# Adafruit_RA8875_TFT_Breakout.net
KiCad netlist of a schematic drawn in EAGLE
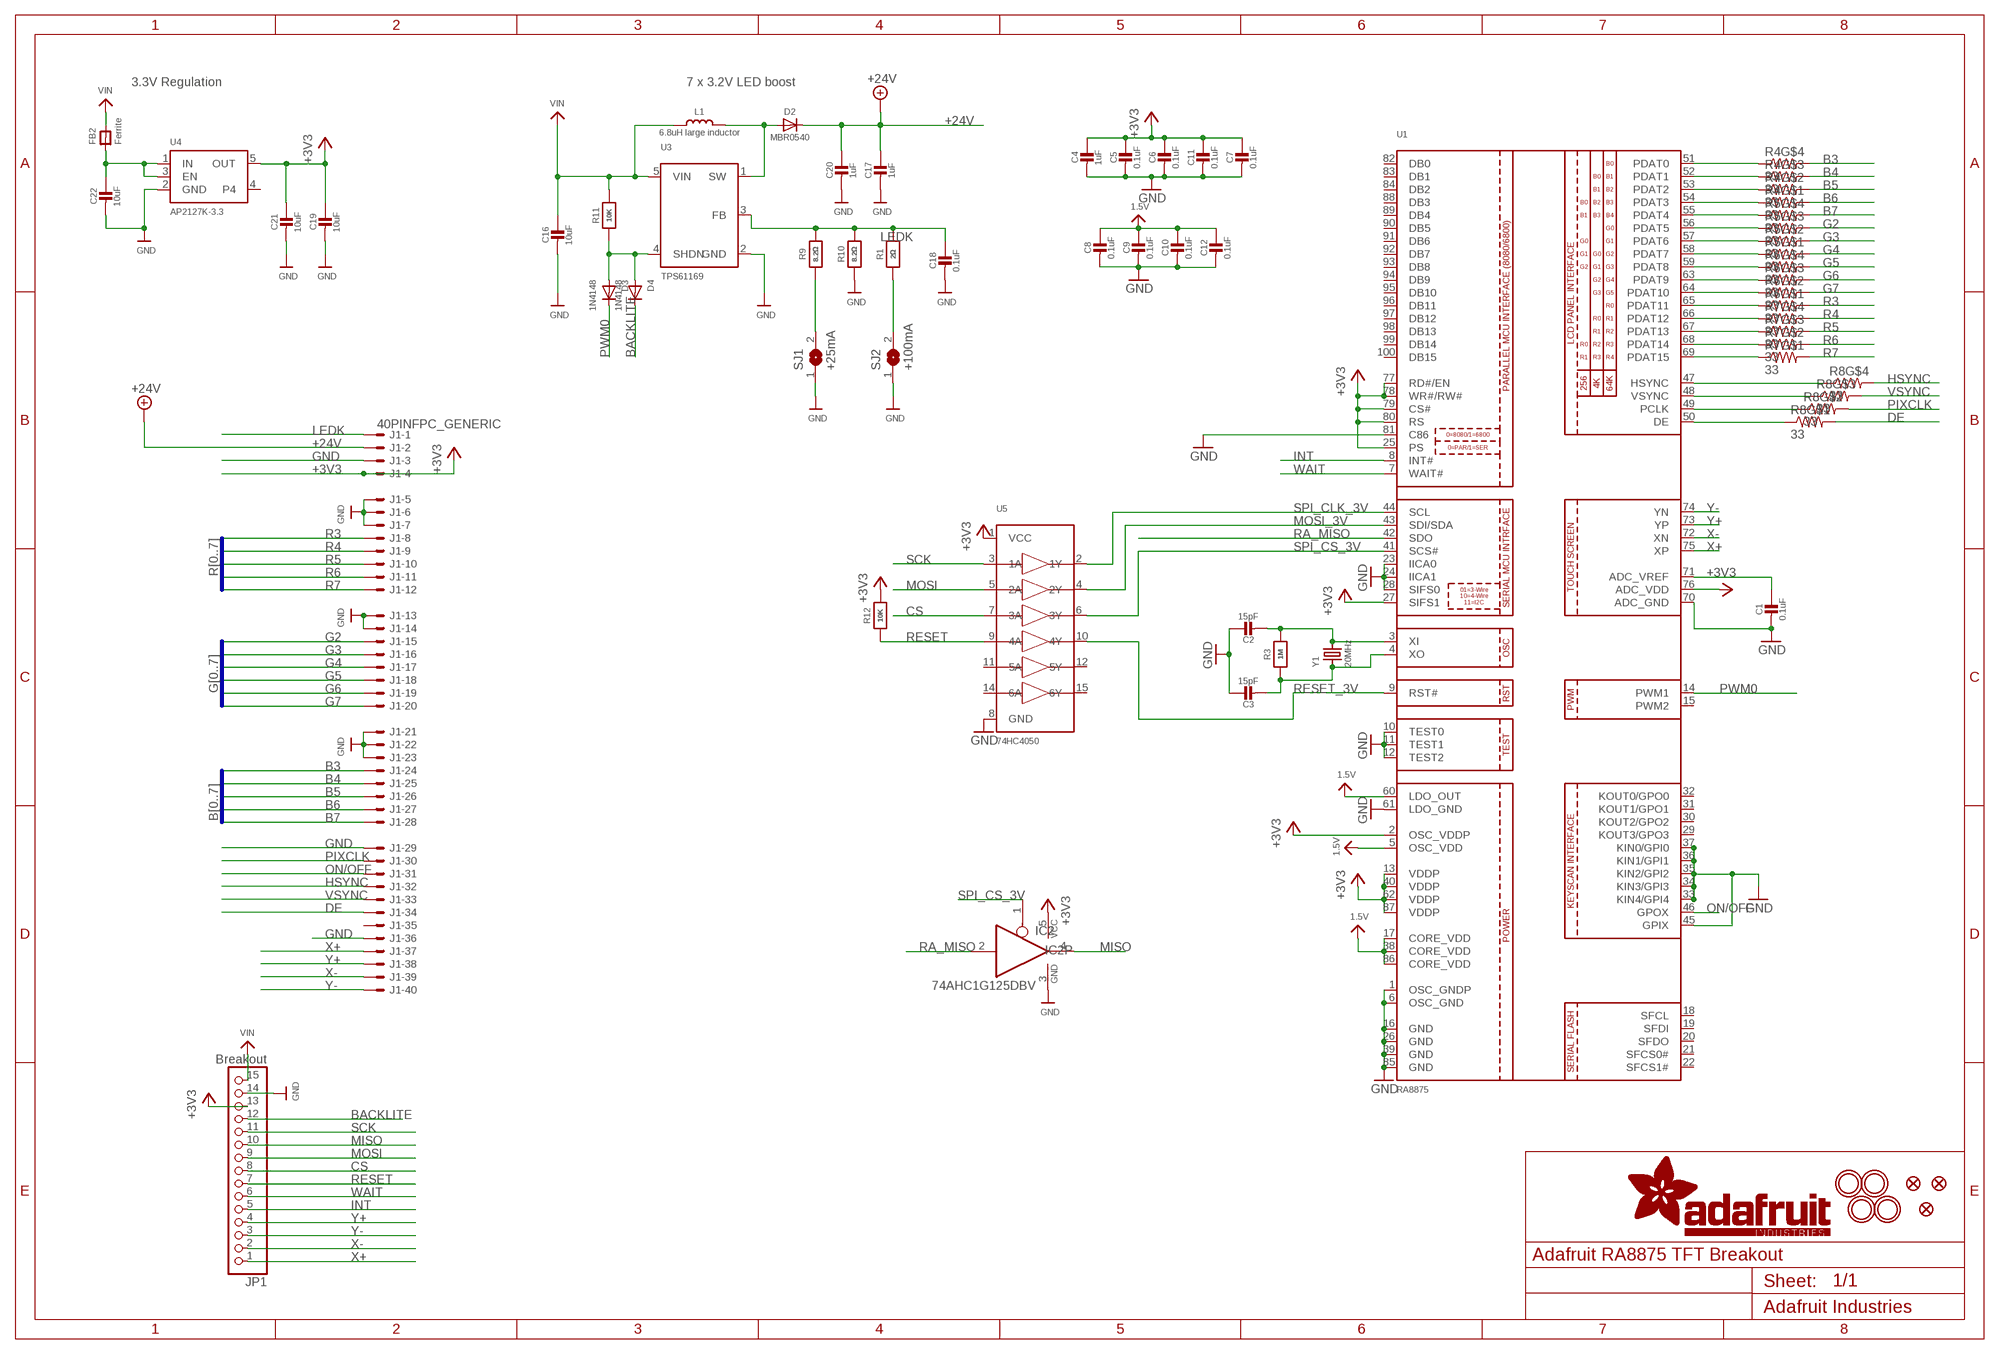
[diagram p0: schematic, sheet 1]

(export (version "E")
  (design (tool "Eeschema 10.0.6"))
  (components
    (comp (ref "C1")
      (value "0.1uF")
      (footprint "eagle-import:0603-NO")
      (libsource (lib "eagle-import") (part "CAP_CERAMIC0603_NO"))
    )
    (comp (ref "C2")
      (value "15pF")
      (footprint "eagle-import:0603-NO")
      (libsource (lib "eagle-import") (part "CAP_CERAMIC0603_NO"))
    )
    (comp (ref "C3")
      (value "15pF")
      (footprint "eagle-import:0603-NO")
      (libsource (lib "eagle-import") (part "CAP_CERAMIC0603_NO"))
    )
    (comp (ref "C4")
      (value "1uF")
      (footprint "eagle-import:0805-NO")
      (libsource (lib "eagle-import") (part "CAP_CERAMIC0805-NOOUTLINE"))
    )
    (comp (ref "C5")
      (value "0.1uF")
      (footprint "eagle-import:0603-NO")
      (libsource (lib "eagle-import") (part "CAP_CERAMIC0603_NO"))
    )
    (comp (ref "C6")
      (value "0.1uF")
      (footprint "eagle-import:0603-NO")
      (libsource (lib "eagle-import") (part "CAP_CERAMIC0603_NO"))
    )
    (comp (ref "C7")
      (value "0.1uF")
      (footprint "eagle-import:0603-NO")
      (libsource (lib "eagle-import") (part "CAP_CERAMIC0603_NO"))
    )
    (comp (ref "C8")
      (value "0.1uF")
      (footprint "eagle-import:0603-NO")
      (libsource (lib "eagle-import") (part "CAP_CERAMIC0603_NO"))
    )
    (comp (ref "C9")
      (value "0.1uF")
      (footprint "eagle-import:0603-NO")
      (libsource (lib "eagle-import") (part "CAP_CERAMIC0603_NO"))
    )
    (comp (ref "C10")
      (value "0.1uF")
      (footprint "eagle-import:0603-NO")
      (libsource (lib "eagle-import") (part "CAP_CERAMIC0603_NO"))
    )
    (comp (ref "C11")
      (value "0.1uF")
      (footprint "eagle-import:0603-NO")
      (libsource (lib "eagle-import") (part "CAP_CERAMIC0603_NO"))
    )
    (comp (ref "C12")
      (value "0.1uF")
      (footprint "eagle-import:0603-NO")
      (libsource (lib "eagle-import") (part "CAP_CERAMIC0603_NO"))
    )
    (comp (ref "C16")
      (value "10uF")
      (footprint "eagle-import:0805-NO")
      (libsource (lib "eagle-import") (part "CAP_CERAMIC0805-NOOUTLINE"))
    )
    (comp (ref "C17")
      (value "1uF")
      (footprint "eagle-import:0805-NO")
      (libsource (lib "eagle-import") (part "CAP_CERAMIC0805-NOOUTLINE"))
    )
    (comp (ref "C18")
      (value "0.1uF")
      (footprint "eagle-import:0603-NO")
      (libsource (lib "eagle-import") (part "CAP_CERAMIC0603_NO"))
    )
    (comp (ref "C19")
      (value "10uF")
      (footprint "eagle-import:0805-NO")
      (libsource (lib "eagle-import") (part "CAP_CERAMIC0805-NOOUTLINE"))
    )
    (comp (ref "C20")
      (value "1uF")
      (footprint "eagle-import:0805-NO")
      (libsource (lib "eagle-import") (part "CAP_CERAMIC0805-NOOUTLINE"))
    )
    (comp (ref "C21")
      (value "10uF")
      (footprint "eagle-import:0805-NO")
      (libsource (lib "eagle-import") (part "CAP_CERAMIC0805-NOOUTLINE"))
    )
    (comp (ref "C22")
      (value "10uF")
      (footprint "eagle-import:0805-NO")
      (libsource (lib "eagle-import") (part "CAP_CERAMIC0805-NOOUTLINE"))
    )
    (comp (ref "D2")
      (value "MBR0540")
      (footprint "eagle-import:SOD-123")
      (libsource (lib "eagle-import") (part "DIODESOD-123"))
    )
    (comp (ref "D3")
      (value "1N4148")
      (footprint "eagle-import:SOD-323_MINI")
      (libsource (lib "eagle-import") (part "DIODE_SOD323MINI"))
    )
    (comp (ref "D4")
      (value "1N4148")
      (footprint "eagle-import:SOD-323_MINI")
      (libsource (lib "eagle-import") (part "DIODE_SOD323MINI"))
    )
    (comp (ref "FB2")
      (value "Ferrite")
      (footprint "eagle-import:0805-NO")
      (libsource (lib "eagle-import") (part "FERRITE-0805NO"))
    )
    (comp (ref "FID1")
      (value "FIDUCIAL_1MM")
      (footprint "eagle-import:FIDUCIAL_1MM")
      (libsource (lib "eagle-import") (part "FIDUCIAL_1MM"))
    )
    (comp (ref "FID2")
      (value "FIDUCIAL_1MM")
      (footprint "eagle-import:FIDUCIAL_1MM")
      (libsource (lib "eagle-import") (part "FIDUCIAL_1MM"))
    )
    (comp (ref "FID3")
      (value "FIDUCIAL_1MM")
      (footprint "eagle-import:FIDUCIAL_1MM")
      (libsource (lib "eagle-import") (part "FIDUCIAL_1MM"))
    )
    (comp (ref "IC2")
      (value "74AHC1G125DBV")
      (footprint "eagle-import:SOT23-5")
      (libsource (lib "eagle-import") (part "741G125DBVAHC"))
    )
    (comp (ref "J1")
      (value "40PINFPC_GENERIC")
      (footprint "eagle-import:FPC_40")
      (libsource (lib "eagle-import") (part "40PINFPC_GENERIC"))
    )
    (comp (ref "JP1")
      (value "Breakout")
      (footprint "eagle-import:1X15-CB")
      (libsource (lib "eagle-import") (part "PINHD-1X15-CB"))
    )
    (comp (ref "L1")
      (value "6.8uH large inductor")
      (footprint "eagle-import:INDUCTOR_5X5MM_NR5040_NOTHERMALS")
      (libsource (lib "eagle-import") (part "INDUCTORNR5040"))
    )
    (comp (ref "R1")
      (value "2Ω")
      (footprint "eagle-import:0805-NO")
      (libsource (lib "eagle-import") (part "RESISTOR0805_NOOUTLINE"))
    )
    (comp (ref "R3")
      (value "1M")
      (footprint "eagle-import:0603-NO")
      (libsource (lib "eagle-import") (part "RESISTOR_0603_NOOUT"))
    )
    (comp (ref "R4")
      (value "33")
      (footprint "eagle-import:RESPACK_4X0603")
      (libsource (lib "eagle-import") (part "RESISTOR_4PACK_US"))
    )
    (comp (ref "R5")
      (value "33")
      (footprint "eagle-import:RESPACK_4X0603")
      (libsource (lib "eagle-import") (part "RESISTOR_4PACK_US"))
    )
    (comp (ref "R6")
      (value "33")
      (footprint "eagle-import:RESPACK_4X0603")
      (libsource (lib "eagle-import") (part "RESISTOR_4PACK_US"))
    )
    (comp (ref "R7")
      (value "33")
      (footprint "eagle-import:RESPACK_4X0603")
      (libsource (lib "eagle-import") (part "RESISTOR_4PACK_US"))
    )
    (comp (ref "R8")
      (value "33")
      (footprint "eagle-import:RESPACK_4X0603")
      (libsource (lib "eagle-import") (part "RESISTOR_4PACK_US"))
    )
    (comp (ref "R9")
      (value "8.2Ω")
      (footprint "eagle-import:0805-NO")
      (libsource (lib "eagle-import") (part "RESISTOR0805_NOOUTLINE"))
    )
    (comp (ref "R10")
      (value "8.2Ω")
      (footprint "eagle-import:0805-NO")
      (libsource (lib "eagle-import") (part "RESISTOR0805_NOOUTLINE"))
    )
    (comp (ref "R11")
      (value "10K")
      (footprint "eagle-import:0603-NO")
      (libsource (lib "eagle-import") (part "RESISTOR_0603_NOOUT"))
    )
    (comp (ref "R12")
      (value "10K")
      (footprint "eagle-import:0603-NO")
      (libsource (lib "eagle-import") (part "RESISTOR_0603_NOOUT"))
    )
    (comp (ref "SJ1")
      (value "+25mA")
      (footprint "eagle-import:SOLDERJUMPER_ARROW_NOPASTE")
      (libsource (lib "eagle-import") (part "SOLDERJUMPER"))
    )
    (comp (ref "SJ2")
      (value "+100mA")
      (footprint "eagle-import:SOLDERJUMPER_ARROW_NOPASTE")
      (fields (field (name "BOM") "EXCLUDE"))
      (libsource (lib "eagle-import") (part "SOLDERJUMPER"))
    )
    (comp (ref "U$21")
      (value "MOUNTINGHOLE2.5")
      (footprint "eagle-import:MOUNTINGHOLE_2.5_PLATED")
      (libsource (lib "eagle-import") (part "MOUNTINGHOLE2.5"))
    )
    (comp (ref "U$22")
      (value "MOUNTINGHOLE2.5")
      (footprint "eagle-import:MOUNTINGHOLE_2.5_PLATED")
      (libsource (lib "eagle-import") (part "MOUNTINGHOLE2.5"))
    )
    (comp (ref "U$23")
      (value "MOUNTINGHOLE2.5")
      (footprint "eagle-import:MOUNTINGHOLE_2.5_PLATED")
      (libsource (lib "eagle-import") (part "MOUNTINGHOLE2.5"))
    )
    (comp (ref "U$24")
      (value "MOUNTINGHOLE2.5")
      (footprint "eagle-import:MOUNTINGHOLE_2.5_PLATED")
      (libsource (lib "eagle-import") (part "MOUNTINGHOLE2.5"))
    )
    (comp (ref "U1")
      (value "RA8875")
      (footprint "eagle-import:LQFP100")
      (libsource (lib "eagle-import") (part "RA8875"))
    )
    (comp (ref "U3")
      (value "TPS61169")
      (footprint "eagle-import:SC70-5")
      (libsource (lib "eagle-import") (part "VREG_BOOST_5PIN_SC70"))
    )
    (comp (ref "U4")
      (value "AP2127K-3.3")
      (footprint "eagle-import:SOT23-5")
      (libsource (lib "eagle-import") (part "VREG_SOT23-5"))
    )
    (comp (ref "U5")
      (value "74HC4050")
      (footprint "eagle-import:TSSOP16")
      (libsource (lib "eagle-import") (part "74HC4050DTSSOP"))
    )
    (comp (ref "Y1")
      (value "20MHz")
      (footprint "eagle-import:CRYSTAL_3.2X2.5")
      (libsource (lib "eagle-import") (part "CRYSTAL3.2X2.5"))
    )
  )
  (nets
    (net (code "9") (name "+3V3") (class "Default")
      (node (ref "C11") (pin "1") (pinfunction "1_1") (pintype "passive"))
      (node (ref "C19") (pin "1") (pinfunction "1_1") (pintype "passive"))
      (node (ref "C21") (pin "1") (pinfunction "1_1") (pintype "passive"))
      (node (ref "C4") (pin "1") (pinfunction "1_1") (pintype "passive"))
      (node (ref "C5") (pin "1") (pinfunction "1_1") (pintype "passive"))
      (node (ref "C6") (pin "1") (pinfunction "1_1") (pintype "passive"))
      (node (ref "C7") (pin "1") (pinfunction "1_1") (pintype "passive"))
      (node (ref "IC2") (pin "5") (pinfunction "VCC_5") (pintype "power_in"))
      (node (ref "J1") (pin "4") (pinfunction "MS_4") (pintype "passive"))
      (node (ref "JP1") (pin "13") (pinfunction "13_13") (pintype "passive"))
      (node (ref "R12") (pin "2") (pinfunction "2_2") (pintype "passive"))
      (node (ref "U1") (pin "13") (pinfunction "VDDP_13") (pintype "power_in"))
      (node (ref "U1") (pin "2") (pinfunction "OSC_VDDP_2") (pintype "power_in"))
      (node (ref "U1") (pin "25") (pinfunction "PS_25") (pintype "input"))
      (node (ref "U1") (pin "27") (pinfunction "SIFS1_27") (pintype "input"))
      (node (ref "U1") (pin "40") (pinfunction "VDDP_40") (pintype "power_in"))
      (node (ref "U1") (pin "62") (pinfunction "VDDP_62") (pintype "power_in"))
      (node (ref "U1") (pin "76") (pinfunction "ADC_VDD_76") (pintype "power_in"))
      (node (ref "U1") (pin "77") (pinfunction "RD#/EN_77") (pintype "input"))
      (node (ref "U1") (pin "78") (pinfunction "WR#/RW#_78") (pintype "input"))
      (node (ref "U1") (pin "79") (pinfunction "CS#_79") (pintype "input"))
      (node (ref "U1") (pin "80") (pinfunction "RS_80") (pintype "input"))
      (node (ref "U1") (pin "87") (pinfunction "VDDP_87") (pintype "power_in"))
      (node (ref "U4") (pin "5") (pinfunction "OUT_5") (pintype "power_in"))
      (node (ref "U5") (pin "1") (pinfunction "VCC_1") (pintype "bidirectional"))
    )
    (net (code "10") (name "+24V") (class "Default")
      (node (ref "C17") (pin "1") (pinfunction "1_1") (pintype "passive"))
      (node (ref "C20") (pin "1") (pinfunction "1_1") (pintype "passive"))
      (node (ref "D2") (pin "C") (pinfunction "C_C") (pintype "passive"))
      (node (ref "J1") (pin "2") (pinfunction "MS_2") (pintype "passive"))
    )
    (net (code "11") (name "/B3") (class "Default")
      (node (ref "J1") (pin "24") (pinfunction "MS_24") (pintype "passive"))
      (node (ref "R4") (pin "5") (pinfunction "2_5") (pintype "passive"))
    )
    (net (code "12") (name "/B4") (class "Default")
      (node (ref "J1") (pin "25") (pinfunction "MS_25") (pintype "passive"))
      (node (ref "R4") (pin "6") (pinfunction "2_6") (pintype "passive"))
    )
    (net (code "13") (name "/B5") (class "Default")
      (node (ref "J1") (pin "26") (pinfunction "MS_26") (pintype "passive"))
      (node (ref "R4") (pin "7") (pinfunction "2_7") (pintype "passive"))
    )
    (net (code "14") (name "/B6") (class "Default")
      (node (ref "J1") (pin "27") (pinfunction "MS_27") (pintype "passive"))
      (node (ref "R4") (pin "8") (pinfunction "2_8") (pintype "passive"))
    )
    (net (code "15") (name "/B7") (class "Default")
      (node (ref "J1") (pin "28") (pinfunction "MS_28") (pintype "passive"))
      (node (ref "R5") (pin "5") (pinfunction "2_5") (pintype "passive"))
    )
    (net (code "16") (name "/BACKLITE") (class "Default")
      (node (ref "D4") (pin "C") (pinfunction "C_C") (pintype "passive"))
      (node (ref "JP1") (pin "12") (pinfunction "12_12") (pintype "passive"))
    )
    (net (code "18") (name "/CS") (class "Default")
      (node (ref "JP1") (pin "8") (pinfunction "8_8") (pintype "passive"))
      (node (ref "U5") (pin "7") (pinfunction "3A_7") (pintype "bidirectional"))
    )
    (net (code "19") (name "/DE") (class "Default")
      (node (ref "J1") (pin "34") (pinfunction "MS_34") (pintype "passive"))
      (node (ref "R8") (pin "8") (pinfunction "2_8") (pintype "passive"))
    )
    (net (code "20") (name "/G2") (class "Default")
      (node (ref "J1") (pin "15") (pinfunction "MS_15") (pintype "passive"))
      (node (ref "R5") (pin "6") (pinfunction "2_6") (pintype "passive"))
    )
    (net (code "21") (name "/G3") (class "Default")
      (node (ref "J1") (pin "16") (pinfunction "MS_16") (pintype "passive"))
      (node (ref "R5") (pin "7") (pinfunction "2_7") (pintype "passive"))
    )
    (net (code "22") (name "/G4") (class "Default")
      (node (ref "J1") (pin "17") (pinfunction "MS_17") (pintype "passive"))
      (node (ref "R5") (pin "8") (pinfunction "2_8") (pintype "passive"))
    )
    (net (code "23") (name "/G5") (class "Default")
      (node (ref "J1") (pin "18") (pinfunction "MS_18") (pintype "passive"))
      (node (ref "R6") (pin "5") (pinfunction "2_5") (pintype "passive"))
    )
    (net (code "24") (name "/G6") (class "Default")
      (node (ref "J1") (pin "19") (pinfunction "MS_19") (pintype "passive"))
      (node (ref "R6") (pin "6") (pinfunction "2_6") (pintype "passive"))
    )
    (net (code "25") (name "/G7") (class "Default")
      (node (ref "J1") (pin "20") (pinfunction "MS_20") (pintype "passive"))
      (node (ref "R6") (pin "7") (pinfunction "2_7") (pintype "passive"))
    )
    (net (code "27") (name "/HSYNC") (class "Default")
      (node (ref "J1") (pin "32") (pinfunction "MS_32") (pintype "passive"))
      (node (ref "R8") (pin "5") (pinfunction "2_5") (pintype "passive"))
    )
    (net (code "28") (name "/INT") (class "Default")
      (node (ref "JP1") (pin "5") (pinfunction "5_5") (pintype "passive"))
      (node (ref "U1") (pin "8") (pinfunction "INT#_8") (pintype "output"))
    )
    (net (code "29") (name "/LEDK") (class "Default")
      (node (ref "C18") (pin "1") (pinfunction "1_1") (pintype "passive"))
      (node (ref "J1") (pin "1") (pinfunction "MSV_1") (pintype "passive"))
      (node (ref "R1") (pin "2") (pinfunction "2_2") (pintype "passive"))
      (node (ref "R10") (pin "2") (pinfunction "2_2") (pintype "passive"))
      (node (ref "R9") (pin "2") (pinfunction "2_2") (pintype "passive"))
      (node (ref "U3") (pin "3") (pinfunction "FB_3") (pintype "bidirectional"))
    )
    (net (code "30") (name "/MISO") (class "Default")
      (node (ref "IC2") (pin "4") (pinfunction "O_4") (pintype "tri_state"))
      (node (ref "JP1") (pin "10") (pinfunction "10_10") (pintype "passive"))
    )
    (net (code "31") (name "/MOSI") (class "Default")
      (node (ref "JP1") (pin "9") (pinfunction "9_9") (pintype "passive"))
      (node (ref "U5") (pin "5") (pinfunction "2A_5") (pintype "bidirectional"))
    )
    (net (code "32") (name "/MOSI_3V") (class "Default")
      (node (ref "U1") (pin "43") (pinfunction "SDI/SDA_43") (pintype "bidirectional"))
      (node (ref "U5") (pin "4") (pinfunction "2Y_4") (pintype "bidirectional"))
    )
    (net (code "33") (name "/ON{slash}OFF") (class "Default")
      (node (ref "J1") (pin "31") (pinfunction "MS_31") (pintype "passive"))
      (node (ref "U1") (pin "46") (pinfunction "GPOX_46") (pintype "output"))
    )
    (net (code "34") (name "/PIXCLK") (class "Default")
      (node (ref "J1") (pin "30") (pinfunction "MS_30") (pintype "passive"))
      (node (ref "R8") (pin "7") (pinfunction "2_7") (pintype "passive"))
    )
    (net (code "35") (name "/PWM0") (class "Default")
      (node (ref "D3") (pin "C") (pinfunction "C_C") (pintype "passive"))
      (node (ref "U1") (pin "14") (pinfunction "PWM1_14") (pintype "output"))
    )
    (net (code "36") (name "/R3") (class "Default")
      (node (ref "J1") (pin "8") (pinfunction "MS_8") (pintype "passive"))
      (node (ref "R6") (pin "8") (pinfunction "2_8") (pintype "passive"))
    )
    (net (code "37") (name "/R4") (class "Default")
      (node (ref "J1") (pin "9") (pinfunction "MS_9") (pintype "passive"))
      (node (ref "R7") (pin "5") (pinfunction "2_5") (pintype "passive"))
    )
    (net (code "38") (name "/R5") (class "Default")
      (node (ref "J1") (pin "10") (pinfunction "MS_10") (pintype "passive"))
      (node (ref "R7") (pin "6") (pinfunction "2_6") (pintype "passive"))
    )
    (net (code "39") (name "/R6") (class "Default")
      (node (ref "J1") (pin "11") (pinfunction "MS_11") (pintype "passive"))
      (node (ref "R7") (pin "7") (pinfunction "2_7") (pintype "passive"))
    )
    (net (code "40") (name "/R7") (class "Default")
      (node (ref "J1") (pin "12") (pinfunction "MS_12") (pintype "passive"))
      (node (ref "R7") (pin "8") (pinfunction "2_8") (pintype "passive"))
    )
    (net (code "41") (name "/RA_MISO") (class "Default")
      (node (ref "IC2") (pin "2") (pinfunction "I_2") (pintype "input"))
      (node (ref "U1") (pin "42") (pinfunction "SDO_42") (pintype "output"))
    )
    (net (code "42") (name "/RESET") (class "Default")
      (node (ref "JP1") (pin "7") (pinfunction "7_7") (pintype "passive"))
      (node (ref "R12") (pin "1") (pinfunction "1_1") (pintype "passive"))
      (node (ref "U5") (pin "9") (pinfunction "4A_9") (pintype "bidirectional"))
    )
    (net (code "43") (name "/RESET_3V") (class "Default")
      (node (ref "U1") (pin "9") (pinfunction "RST#_9") (pintype "input"))
      (node (ref "U5") (pin "10") (pinfunction "4Y_10") (pintype "bidirectional"))
    )
    (net (code "45") (name "/SCK") (class "Default")
      (node (ref "JP1") (pin "11") (pinfunction "11_11") (pintype "passive"))
      (node (ref "U5") (pin "3") (pinfunction "1A_3") (pintype "bidirectional"))
    )
    (net (code "46") (name "/SPI_CLK_3V") (class "Default")
      (node (ref "U1") (pin "44") (pinfunction "SCL_44") (pintype "output"))
      (node (ref "U5") (pin "2") (pinfunction "1Y_2") (pintype "bidirectional"))
    )
    (net (code "47") (name "/SPI_CS_3V") (class "Default")
      (node (ref "IC2") (pin "1") (pinfunction "OE_1") (pintype "input"))
      (node (ref "U1") (pin "41") (pinfunction "SCS#_41") (pintype "output"))
      (node (ref "U5") (pin "6") (pinfunction "3Y_6") (pintype "bidirectional"))
    )
    (net (code "48") (name "/VSYNC") (class "Default")
      (node (ref "J1") (pin "33") (pinfunction "MS_33") (pintype "passive"))
      (node (ref "R8") (pin "6") (pinfunction "2_6") (pintype "passive"))
    )
    (net (code "49") (name "/WAIT") (class "Default")
      (node (ref "JP1") (pin "6") (pinfunction "6_6") (pintype "passive"))
      (node (ref "U1") (pin "7") (pinfunction "WAIT#_7") (pintype "output"))
    )
    (net (code "50") (name "/X+") (class "Default")
      (node (ref "J1") (pin "37") (pinfunction "MS_37") (pintype "passive"))
      (node (ref "JP1") (pin "1") (pinfunction "1_1") (pintype "passive"))
      (node (ref "U1") (pin "75") (pinfunction "XP_75") (pintype "bidirectional"))
    )
    (net (code "51") (name "/X-") (class "Default")
      (node (ref "J1") (pin "39") (pinfunction "MS_39") (pintype "passive"))
      (node (ref "JP1") (pin "2") (pinfunction "2_2") (pintype "passive"))
      (node (ref "U1") (pin "72") (pinfunction "XN_72") (pintype "bidirectional"))
    )
    (net (code "52") (name "/Y+") (class "Default")
      (node (ref "J1") (pin "38") (pinfunction "MS_38") (pintype "passive"))
      (node (ref "JP1") (pin "4") (pinfunction "4_4") (pintype "passive"))
      (node (ref "U1") (pin "73") (pinfunction "YP_73") (pintype "bidirectional"))
    )
    (net (code "53") (name "/Y-") (class "Default")
      (node (ref "J1") (pin "40") (pinfunction "MS_40") (pintype "passive"))
      (node (ref "JP1") (pin "3") (pinfunction "3_3") (pintype "passive"))
      (node (ref "U1") (pin "74") (pinfunction "YN_74") (pintype "bidirectional"))
    )
    (net (code "54") (name "1.5V") (class "Default")
      (node (ref "C10") (pin "1") (pinfunction "1_1") (pintype "passive"))
      (node (ref "C12") (pin "1") (pinfunction "1_1") (pintype "passive"))
      (node (ref "C8") (pin "1") (pinfunction "1_1") (pintype "passive"))
      (node (ref "C9") (pin "1") (pinfunction "1_1") (pintype "passive"))
      (node (ref "U1") (pin "17") (pinfunction "CORE_VDD_17") (pintype "power_in"))
      (node (ref "U1") (pin "38") (pinfunction "CORE_VDD_38") (pintype "power_in"))
      (node (ref "U1") (pin "5") (pinfunction "OSC_VDD_5") (pintype "power_in"))
      (node (ref "U1") (pin "60") (pinfunction "LDO_OUT_60") (pintype "power_in"))
      (node (ref "U1") (pin "86") (pinfunction "CORE_VDD_86") (pintype "power_in"))
    )
    (net (code "55") (name "GND") (class "Default")
      (node (ref "C1") (pin "2") (pinfunction "2_2") (pintype "passive"))
      (node (ref "C10") (pin "2") (pinfunction "2_2") (pintype "passive"))
      (node (ref "C11") (pin "2") (pinfunction "2_2") (pintype "passive"))
      (node (ref "C12") (pin "2") (pinfunction "2_2") (pintype "passive"))
      (node (ref "C16") (pin "2") (pinfunction "2_2") (pintype "passive"))
      (node (ref "C17") (pin "2") (pinfunction "2_2") (pintype "passive"))
      (node (ref "C18") (pin "2") (pinfunction "2_2") (pintype "passive"))
      (node (ref "C19") (pin "2") (pinfunction "2_2") (pintype "passive"))
      (node (ref "C2") (pin "1") (pinfunction "1_1") (pintype "passive"))
      (node (ref "C20") (pin "2") (pinfunction "2_2") (pintype "passive"))
      (node (ref "C21") (pin "2") (pinfunction "2_2") (pintype "passive"))
      (node (ref "C22") (pin "2") (pinfunction "2_2") (pintype "passive"))
      (node (ref "C3") (pin "1") (pinfunction "1_1") (pintype "passive"))
      (node (ref "C4") (pin "2") (pinfunction "2_2") (pintype "passive"))
      (node (ref "C5") (pin "2") (pinfunction "2_2") (pintype "passive"))
      (node (ref "C6") (pin "2") (pinfunction "2_2") (pintype "passive"))
      (node (ref "C7") (pin "2") (pinfunction "2_2") (pintype "passive"))
      (node (ref "C8") (pin "2") (pinfunction "2_2") (pintype "passive"))
      (node (ref "C9") (pin "2") (pinfunction "2_2") (pintype "passive"))
      (node (ref "IC2") (pin "3") (pinfunction "GND_3") (pintype "power_in"))
      (node (ref "J1") (pin "13") (pinfunction "MS_13") (pintype "passive"))
      (node (ref "J1") (pin "14") (pinfunction "MS_14") (pintype "passive"))
      (node (ref "J1") (pin "21") (pinfunction "MS_21") (pintype "passive"))
      (node (ref "J1") (pin "22") (pinfunction "MS_22") (pintype "passive"))
      (node (ref "J1") (pin "23") (pinfunction "MS_23") (pintype "passive"))
      (node (ref "J1") (pin "29") (pinfunction "MS_29") (pintype "passive"))
      (node (ref "J1") (pin "3") (pinfunction "MS_3") (pintype "passive"))
      (node (ref "J1") (pin "36") (pinfunction "MS_36") (pintype "passive"))
      (node (ref "J1") (pin "5") (pinfunction "MS_5") (pintype "passive"))
      (node (ref "J1") (pin "6") (pinfunction "MS_6") (pintype "passive"))
      (node (ref "J1") (pin "7") (pinfunction "MS_7") (pintype "passive"))
      (node (ref "JP1") (pin "14") (pinfunction "14_14") (pintype "passive"))
      (node (ref "R10") (pin "1") (pinfunction "1_1") (pintype "passive"))
      (node (ref "SJ1") (pin "1") (pinfunction "1_1") (pintype "passive"))
      (node (ref "SJ2") (pin "1") (pinfunction "1_1") (pintype "passive"))
      (node (ref "U1") (pin "1") (pinfunction "OSC_GNDP_1") (pintype "power_in"))
      (node (ref "U1") (pin "10") (pinfunction "TEST0_10") (pintype "input"))
      (node (ref "U1") (pin "11") (pinfunction "TEST1_11") (pintype "input"))
      (node (ref "U1") (pin "12") (pinfunction "TEST2_12") (pintype "input"))
      (node (ref "U1") (pin "16") (pinfunction "GND_16") (pintype "power_in"))
      (node (ref "U1") (pin "23") (pinfunction "IICA0_23") (pintype "input"))
      (node (ref "U1") (pin "24") (pinfunction "IICA1_24") (pintype "input"))
      (node (ref "U1") (pin "26") (pinfunction "GND_26") (pintype "power_in"))
      (node (ref "U1") (pin "28") (pinfunction "SIFS0_28") (pintype "input"))
      (node (ref "U1") (pin "33") (pinfunction "KIN4/GPI4_33") (pintype "input"))
      (node (ref "U1") (pin "34") (pinfunction "KIN3/GPI3_34") (pintype "input"))
      (node (ref "U1") (pin "35") (pinfunction "KIN2/GPI2_35") (pintype "input"))
      (node (ref "U1") (pin "36") (pinfunction "KIN1/GPI1_36") (pintype "input"))
      (node (ref "U1") (pin "37") (pinfunction "KIN0/GPI0_37") (pintype "input"))
      (node (ref "U1") (pin "39") (pinfunction "GND_39") (pintype "power_in"))
      (node (ref "U1") (pin "45") (pinfunction "GPIX_45") (pintype "input"))
      (node (ref "U1") (pin "6") (pinfunction "OSC_GND_6") (pintype "power_in"))
      (node (ref "U1") (pin "61") (pinfunction "LDO_GND_61") (pintype "power_in"))
      (node (ref "U1") (pin "70") (pinfunction "ADC_GND_70") (pintype "power_in"))
      (node (ref "U1") (pin "81") (pinfunction "C86_81") (pintype "input"))
      (node (ref "U1") (pin "85") (pinfunction "GND_85") (pintype "power_in"))
      (node (ref "U3") (pin "2") (pinfunction "GND_2") (pintype "bidirectional"))
      (node (ref "U4") (pin "2") (pinfunction "GND_2") (pintype "power_in"))
      (node (ref "U5") (pin "8") (pinfunction "GND_8") (pintype "bidirectional"))
    )
    (net (code "56") (name "Net-(FB2-P$1)") (class "Default")
      (node (ref "C22") (pin "1") (pinfunction "1_1") (pintype "passive"))
      (node (ref "FB2") (pin "1") (pinfunction "P$1_1") (pintype "passive"))
      (node (ref "U4") (pin "1") (pinfunction "IN_1") (pintype "power_in"))
      (node (ref "U4") (pin "3") (pinfunction "EN_3") (pintype "input"))
    )
    (net (code "57") (name "Net-(L1-2)") (class "Default")
      (node (ref "D2") (pin "A") (pinfunction "A_A") (pintype "passive"))
      (node (ref "L1") (pin "P$2") (pinfunction "2_P$2") (pintype "passive"))
      (node (ref "U3") (pin "1") (pinfunction "SW_1") (pintype "bidirectional"))
    )
    (net (code "58") (name "Net-(R1-Pad1)") (class "Default")
      (node (ref "R1") (pin "1") (pinfunction "1_1") (pintype "passive"))
      (node (ref "SJ2") (pin "2") (pinfunction "2_2") (pintype "passive"))
    )
    (net (code "59") (name "Net-(R4B-1)") (class "Default")
      (node (ref "R4") (pin "2") (pinfunction "1_2") (pintype "passive"))
      (node (ref "U1") (pin "53") (pinfunction "PDAT2_53") (pintype "output"))
    )
    (net (code "60") (name "Net-(R4C-1)") (class "Default")
      (node (ref "R4") (pin "3") (pinfunction "1_3") (pintype "passive"))
      (node (ref "U1") (pin "52") (pinfunction "PDAT1_52") (pintype "output"))
    )
    (net (code "61") (name "Net-(R4D-1)") (class "Default")
      (node (ref "R4") (pin "4") (pinfunction "1_4") (pintype "passive"))
      (node (ref "U1") (pin "51") (pinfunction "PDAT0_51") (pintype "output"))
    )
    (net (code "62") (name "Net-(R5B-1)") (class "Default")
      (node (ref "R5") (pin "2") (pinfunction "1_2") (pintype "passive"))
      (node (ref "U1") (pin "57") (pinfunction "PDAT6_57") (pintype "output"))
    )
    (net (code "63") (name "Net-(R5C-1)") (class "Default")
      (node (ref "R5") (pin "3") (pinfunction "1_3") (pintype "passive"))
      (node (ref "U1") (pin "56") (pinfunction "PDAT5_56") (pintype "output"))
    )
    (net (code "64") (name "Net-(R5D-1)") (class "Default")
      (node (ref "R5") (pin "4") (pinfunction "1_4") (pintype "passive"))
      (node (ref "U1") (pin "55") (pinfunction "PDAT4_55") (pintype "output"))
    )
    (net (code "65") (name "Net-(R6B-1)") (class "Default")
      (node (ref "R6") (pin "2") (pinfunction "1_2") (pintype "passive"))
      (node (ref "U1") (pin "64") (pinfunction "PDAT10_64") (pintype "output"))
    )
    (net (code "66") (name "Net-(R6C-1)") (class "Default")
      (node (ref "R6") (pin "3") (pinfunction "1_3") (pintype "passive"))
      (node (ref "U1") (pin "63") (pinfunction "PDAT9_63") (pintype "output"))
    )
    (net (code "67") (name "Net-(R6D-1)") (class "Default")
      (node (ref "R6") (pin "4") (pinfunction "1_4") (pintype "passive"))
      (node (ref "U1") (pin "59") (pinfunction "PDAT8_59") (pintype "output"))
    )
    (net (code "68") (name "Net-(R7B-1)") (class "Default")
      (node (ref "R7") (pin "2") (pinfunction "1_2") (pintype "passive"))
      (node (ref "U1") (pin "68") (pinfunction "PDAT14_68") (pintype "output"))
    )
    (net (code "69") (name "Net-(R7C-1)") (class "Default")
      (node (ref "R7") (pin "3") (pinfunction "1_3") (pintype "passive"))
      (node (ref "U1") (pin "67") (pinfunction "PDAT13_67") (pintype "output"))
    )
    (net (code "70") (name "Net-(R7D-1)") (class "Default")
      (node (ref "R7") (pin "4") (pinfunction "1_4") (pintype "passive"))
      (node (ref "U1") (pin "66") (pinfunction "PDAT12_66") (pintype "output"))
    )
    (net (code "71") (name "Net-(R8B-1)") (class "Default")
      (node (ref "R8") (pin "2") (pinfunction "1_2") (pintype "passive"))
      (node (ref "U1") (pin "49") (pinfunction "PCLK_49") (pintype "output"))
    )
    (net (code "72") (name "Net-(R8C-1)") (class "Default")
      (node (ref "R8") (pin "3") (pinfunction "1_3") (pintype "passive"))
      (node (ref "U1") (pin "48") (pinfunction "VSYNC_48") (pintype "output"))
    )
    (net (code "73") (name "Net-(R8D-1)") (class "Default")
      (node (ref "R8") (pin "4") (pinfunction "1_4") (pintype "passive"))
      (node (ref "U1") (pin "47") (pinfunction "HSYNC_47") (pintype "output"))
    )
    (net (code "74") (name "Net-(R9-Pad1)") (class "Default")
      (node (ref "R9") (pin "1") (pinfunction "1_1") (pintype "passive"))
      (node (ref "SJ1") (pin "2") (pinfunction "2_2") (pintype "passive"))
    )
    (net (code "75") (name "Net-(U1-ADC_VREF)") (class "Default")
      (node (ref "C1") (pin "1") (pinfunction "1_1") (pintype "passive"))
      (node (ref "U1") (pin "71") (pinfunction "ADC_VREF_71") (pintype "input"))
    )
    (net (code "76") (name "Net-(U1-DE)") (class "Default")
      (node (ref "R8") (pin "1") (pinfunction "1_1") (pintype "passive"))
      (node (ref "U1") (pin "50") (pinfunction "DE_50") (pintype "output"))
    )
    (net (code "77") (name "Net-(U1-PDAT3)") (class "Default")
      (node (ref "R4") (pin "1") (pinfunction "1_1") (pintype "passive"))
      (node (ref "U1") (pin "54") (pinfunction "PDAT3_54") (pintype "output"))
    )
    (net (code "78") (name "Net-(U1-PDAT7)") (class "Default")
      (node (ref "R5") (pin "1") (pinfunction "1_1") (pintype "passive"))
      (node (ref "U1") (pin "58") (pinfunction "PDAT7_58") (pintype "output"))
    )
    (net (code "79") (name "Net-(U1-PDAT11)") (class "Default")
      (node (ref "R6") (pin "1") (pinfunction "1_1") (pintype "passive"))
      (node (ref "U1") (pin "65") (pinfunction "PDAT11_65") (pintype "output"))
    )
    (net (code "80") (name "Net-(U1-PDAT15)") (class "Default")
      (node (ref "R7") (pin "1") (pinfunction "1_1") (pintype "passive"))
      (node (ref "U1") (pin "69") (pinfunction "PDAT15_69") (pintype "output"))
    )
    (net (code "81") (name "Net-(U1-XI)") (class "Default")
      (node (ref "C2") (pin "2") (pinfunction "2_2") (pintype "passive"))
      (node (ref "R3") (pin "2") (pinfunction "2_2") (pintype "passive"))
      (node (ref "U1") (pin "3") (pinfunction "XI_3") (pintype "input"))
      (node (ref "Y1") (pin "2") (pinfunction "2_2") (pintype "passive"))
    )
    (net (code "82") (name "Net-(U1-XO)") (class "Default")
      (node (ref "C3") (pin "2") (pinfunction "2_2") (pintype "passive"))
      (node (ref "R3") (pin "1") (pinfunction "1_1") (pintype "passive"))
      (node (ref "U1") (pin "4") (pinfunction "XO_4") (pintype "output"))
      (node (ref "Y1") (pin "1") (pinfunction "1_1") (pintype "passive"))
    )
    (net (code "83") (name "Net-(U3-SHDN)") (class "Default")
      (node (ref "D3") (pin "A") (pinfunction "A_A") (pintype "passive"))
      (node (ref "D4") (pin "A") (pinfunction "A_A") (pintype "passive"))
      (node (ref "R11") (pin "1") (pinfunction "1_1") (pintype "passive"))
      (node (ref "U3") (pin "4") (pinfunction "SHDN_4") (pintype "bidirectional"))
    )
    (net (code "84") (name "VIN") (class "Default")
      (node (ref "C16") (pin "1") (pinfunction "1_1") (pintype "passive"))
      (node (ref "FB2") (pin "2") (pinfunction "P$2_2") (pintype "passive"))
      (node (ref "JP1") (pin "15") (pinfunction "15_15") (pintype "passive"))
      (node (ref "L1") (pin "P$1") (pinfunction "1_P$1") (pintype "passive"))
      (node (ref "R11") (pin "2") (pinfunction "2_2") (pintype "passive"))
      (node (ref "U3") (pin "5") (pinfunction "VIN_5") (pintype "bidirectional"))
    )
    (net (code "85") (name "unconnected-(J1AC-MS-Pad35)") (class "Default")
      (node (ref "J1") (pin "35") (pinfunction "MS_35") (pintype "passive"))
    )
    (net (code "86") (name "unconnected-(U1-DB0-Pad82)") (class "Default")
      (node (ref "U1") (pin "82") (pinfunction "DB0_82") (pintype "bidirectional"))
    )
    (net (code "87") (name "unconnected-(U1-DB1-Pad83)") (class "Default")
      (node (ref "U1") (pin "83") (pinfunction "DB1_83") (pintype "bidirectional"))
    )
    (net (code "88") (name "unconnected-(U1-DB2-Pad84)") (class "Default")
      (node (ref "U1") (pin "84") (pinfunction "DB2_84") (pintype "bidirectional"))
    )
    (net (code "89") (name "unconnected-(U1-DB3-Pad88)") (class "Default")
      (node (ref "U1") (pin "88") (pinfunction "DB3_88") (pintype "bidirectional"))
    )
    (net (code "90") (name "unconnected-(U1-DB4-Pad89)") (class "Default")
      (node (ref "U1") (pin "89") (pinfunction "DB4_89") (pintype "bidirectional"))
    )
    (net (code "91") (name "unconnected-(U1-DB5-Pad90)") (class "Default")
      (node (ref "U1") (pin "90") (pinfunction "DB5_90") (pintype "bidirectional"))
    )
    (net (code "92") (name "unconnected-(U1-DB6-Pad91)") (class "Default")
      (node (ref "U1") (pin "91") (pinfunction "DB6_91") (pintype "bidirectional"))
    )
    (net (code "93") (name "unconnected-(U1-DB7-Pad92)") (class "Default")
      (node (ref "U1") (pin "92") (pinfunction "DB7_92") (pintype "bidirectional"))
    )
    (net (code "94") (name "unconnected-(U1-DB8-Pad93)") (class "Default")
      (node (ref "U1") (pin "93") (pinfunction "DB8_93") (pintype "bidirectional"))
    )
    (net (code "95") (name "unconnected-(U1-DB9-Pad94)") (class "Default")
      (node (ref "U1") (pin "94") (pinfunction "DB9_94") (pintype "bidirectional"))
    )
    (net (code "96") (name "unconnected-(U1-DB10-Pad95)") (class "Default")
      (node (ref "U1") (pin "95") (pinfunction "DB10_95") (pintype "bidirectional"))
    )
    (net (code "97") (name "unconnected-(U1-DB11-Pad96)") (class "Default")
      (node (ref "U1") (pin "96") (pinfunction "DB11_96") (pintype "bidirectional"))
    )
    (net (code "98") (name "unconnected-(U1-DB12-Pad97)") (class "Default")
      (node (ref "U1") (pin "97") (pinfunction "DB12_97") (pintype "bidirectional"))
    )
    (net (code "99") (name "unconnected-(U1-DB13-Pad98)") (class "Default")
      (node (ref "U1") (pin "98") (pinfunction "DB13_98") (pintype "bidirectional"))
    )
    (net (code "100") (name "unconnected-(U1-DB14-Pad99)") (class "Default")
      (node (ref "U1") (pin "99") (pinfunction "DB14_99") (pintype "bidirectional"))
    )
    (net (code "101") (name "unconnected-(U1-DB15-Pad100)") (class "Default")
      (node (ref "U1") (pin "100") (pinfunction "DB15_100") (pintype "bidirectional"))
    )
    (net (code "102") (name "unconnected-(U1-KOUT0{slash}GPO0-Pad32)") (class "Default")
      (node (ref "U1") (pin "32") (pinfunction "KOUT0/GPO0_32") (pintype "output"))
    )
    (net (code "103") (name "unconnected-(U1-KOUT1{slash}GPO1-Pad31)") (class "Default")
      (node (ref "U1") (pin "31") (pinfunction "KOUT1/GPO1_31") (pintype "output"))
    )
    (net (code "104") (name "unconnected-(U1-KOUT2{slash}GPO2-Pad30)") (class "Default")
      (node (ref "U1") (pin "30") (pinfunction "KOUT2/GPO2_30") (pintype "output"))
    )
    (net (code "105") (name "unconnected-(U1-KOUT3{slash}GPO3-Pad29)") (class "Default")
      (node (ref "U1") (pin "29") (pinfunction "KOUT3/GPO3_29") (pintype "output"))
    )
    (net (code "106") (name "unconnected-(U1-PWM2-Pad15)") (class "Default")
      (node (ref "U1") (pin "15") (pinfunction "PWM2_15") (pintype "output"))
    )
    (net (code "107") (name "unconnected-(U1-SFCL-Pad18)") (class "Default")
      (node (ref "U1") (pin "18") (pinfunction "SFCL_18") (pintype "output"))
    )
    (net (code "108") (name "unconnected-(U1-SFCS0#-Pad21)") (class "Default")
      (node (ref "U1") (pin "21") (pinfunction "SFCS0#_21") (pintype "output"))
    )
    (net (code "109") (name "unconnected-(U1-SFCS1#-Pad22)") (class "Default")
      (node (ref "U1") (pin "22") (pinfunction "SFCS1#_22") (pintype "output"))
    )
    (net (code "110") (name "unconnected-(U1-SFDI-Pad19)") (class "Default")
      (node (ref "U1") (pin "19") (pinfunction "SFDI_19") (pintype "bidirectional"))
    )
    (net (code "111") (name "unconnected-(U1-SFDO-Pad20)") (class "Default")
      (node (ref "U1") (pin "20") (pinfunction "SFDO_20") (pintype "bidirectional"))
    )
    (net (code "112") (name "unconnected-(U4-P4-Pad4)") (class "Default")
      (node (ref "U4") (pin "4") (pinfunction "P4_4") (pintype "bidirectional"))
    )
    (net (code "113") (name "unconnected-(U5-5A-Pad11)") (class "Default")
      (node (ref "U5") (pin "11") (pinfunction "5A_11") (pintype "bidirectional"))
    )
    (net (code "114") (name "unconnected-(U5-5Y-Pad12)") (class "Default")
      (node (ref "U5") (pin "12") (pinfunction "5Y_12") (pintype "bidirectional"))
    )
    (net (code "115") (name "unconnected-(U5-6A-Pad14)") (class "Default")
      (node (ref "U5") (pin "14") (pinfunction "6A_14") (pintype "bidirectional"))
    )
    (net (code "116") (name "unconnected-(U5-6Y-Pad15)") (class "Default")
      (node (ref "U5") (pin "15") (pinfunction "6Y_15") (pintype "bidirectional"))
    )
  )
)
